# 433hw2.net
KiCad netlist of a schematic drawn in EAGLE
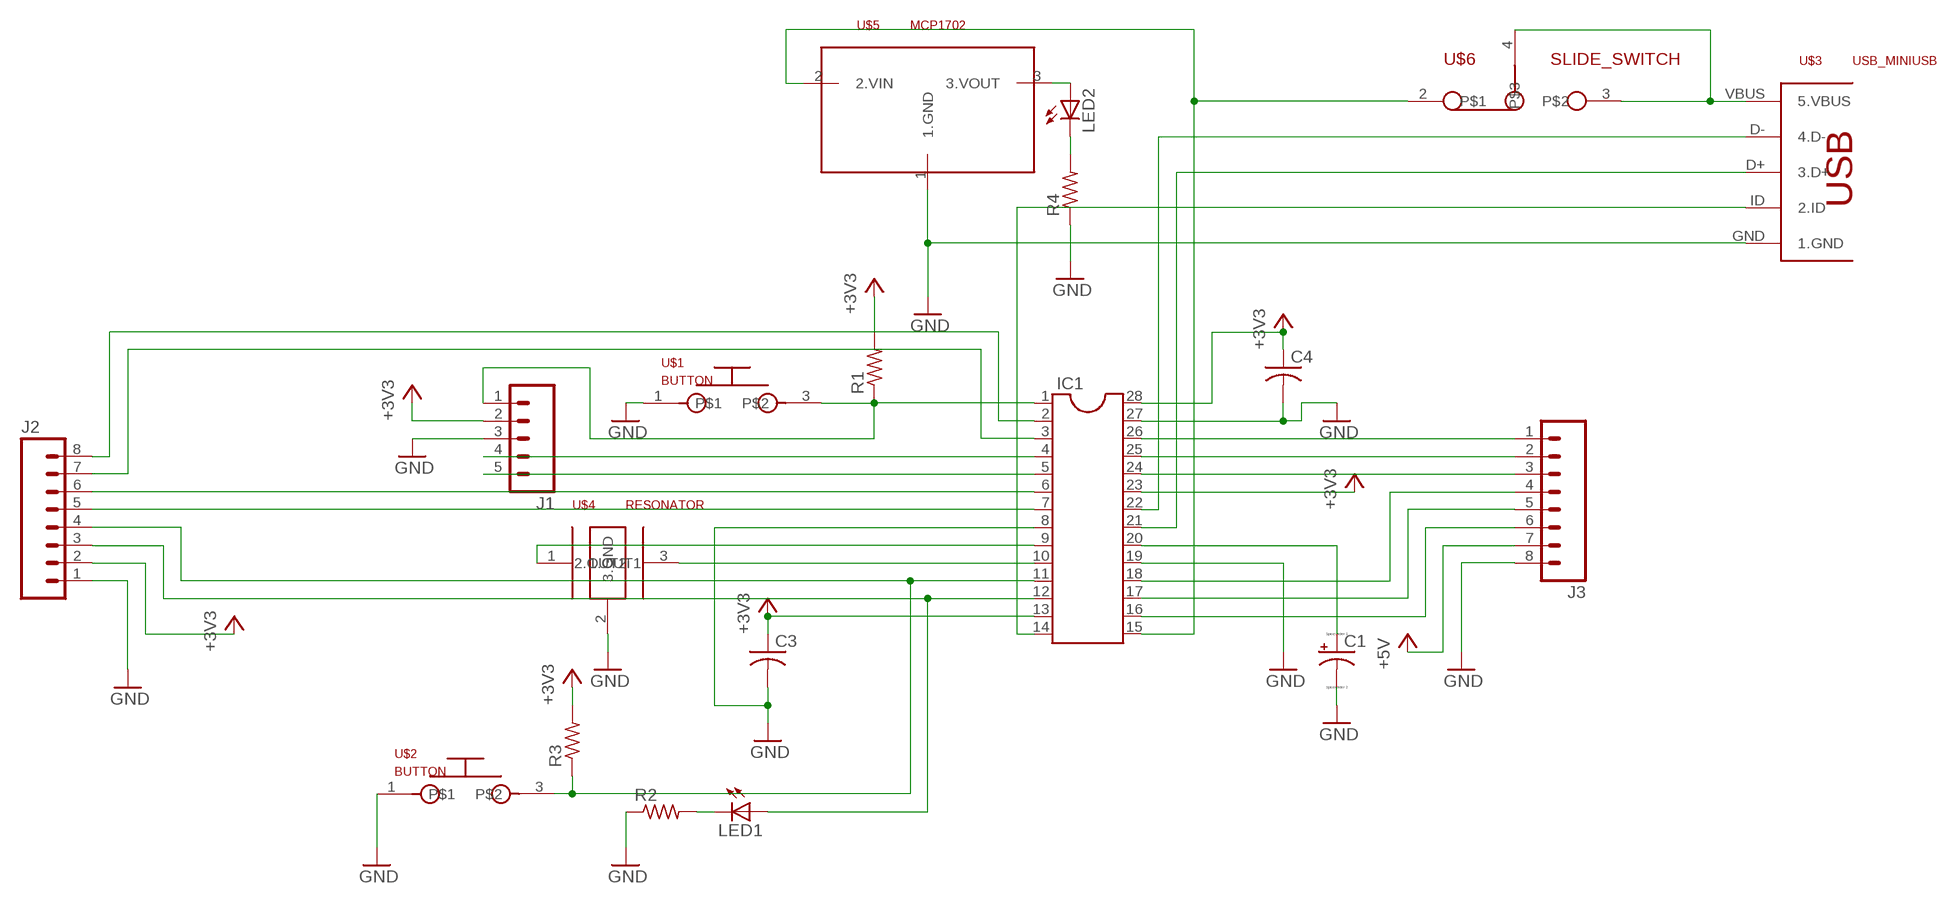
[diagram p0: schematic, sheet 1]

(export (version "E")
  (design (tool "Eeschema 10.0.6"))
  (components
    (comp (ref "C1")
      (value "CPOL-USE2.5-6")
      (footprint "eagle-import:E2,5-6")
      (libsource (lib "eagle-import") (part "CPOL-USE2.5-6"))
    )
    (comp (ref "C3")
      (value "C-US025-025X050")
      (footprint "eagle-import:C025-025X050")
      (libsource (lib "eagle-import") (part "C-US025-025X050"))
    )
    (comp (ref "C4")
      (value "C-US025-025X050")
      (footprint "eagle-import:C025-025X050")
      (libsource (lib "eagle-import") (part "C-US025-025X050"))
    )
    (comp (ref "IC1")
      (value "DIL28-4")
      (footprint "eagle-import:DIL28-4")
      (libsource (lib "eagle-import") (part "DIL28-4"))
    )
    (comp (ref "J1")
      (value "M05PTH")
      (footprint "eagle-import:1X05")
      (libsource (lib "eagle-import") (part "M05PTH"))
    )
    (comp (ref "J2")
      (value "M08")
      (footprint "eagle-import:1X08_ROUND")
      (libsource (lib "eagle-import") (part "M08"))
    )
    (comp (ref "J3")
      (value "M08")
      (footprint "eagle-import:1X08_ROUND")
      (libsource (lib "eagle-import") (part "M08"))
    )
    (comp (ref "LED1")
      (value "LED3MM")
      (footprint "eagle-import:LED3MM")
      (libsource (lib "eagle-import") (part "LED3MM"))
    )
    (comp (ref "LED2")
      (value "LED3MM")
      (footprint "eagle-import:LED3MM")
      (libsource (lib "eagle-import") (part "LED3MM"))
    )
    (comp (ref "R1")
      (value "R-US_0207/7")
      (footprint "eagle-import:0207_7")
      (libsource (lib "eagle-import") (part "R-US_0207/7"))
    )
    (comp (ref "R2")
      (value "R-US_0207/7")
      (footprint "eagle-import:0207_7")
      (libsource (lib "eagle-import") (part "R-US_0207/7"))
    )
    (comp (ref "R3")
      (value "R-US_0207/7")
      (footprint "eagle-import:0207_7")
      (libsource (lib "eagle-import") (part "R-US_0207/7"))
    )
    (comp (ref "R4")
      (value "R-US_0207/7")
      (footprint "eagle-import:0207_7")
      (libsource (lib "eagle-import") (part "R-US_0207/7"))
    )
    (comp (ref "U$1")
      (value "BUTTON")
      (footprint "eagle-import:BUTTON")
      (libsource (lib "eagle-import") (part "BUTTON"))
    )
    (comp (ref "U$2")
      (value "BUTTON")
      (footprint "eagle-import:BUTTON")
      (libsource (lib "eagle-import") (part "BUTTON"))
    )
    (comp (ref "U$3")
      (value "USB_MINIUSB")
      (footprint "eagle-import:USB-MB-H")
      (libsource (lib "eagle-import") (part "USB_MINIUSB"))
    )
    (comp (ref "U$4")
      (value "RESONATOR")
      (footprint "eagle-import:1X03")
      (libsource (lib "eagle-import") (part "RESONATOR"))
    )
    (comp (ref "U$5")
      (value "MCP1702")
      (footprint "eagle-import:TO92")
      (libsource (lib "eagle-import") (part "MCP1702"))
    )
    (comp (ref "U$6")
      (value "SLIDE_SWITCH")
      (footprint "eagle-import:1X05")
      (libsource (lib "eagle-import") (part "SLIDE_SWITCH"))
    )
  )
  (nets
    (net (code "1") (name "+3V3") (class "Default")
      (node (ref "C3") (pin "1") (pinfunction "1_1") (pintype "passive"))
      (node (ref "C4") (pin "1") (pinfunction "1_1") (pintype "passive"))
      (node (ref "IC1") (pin "13") (pinfunction "13_13") (pintype "passive"))
      (node (ref "IC1") (pin "23") (pinfunction "23_23") (pintype "passive"))
      (node (ref "IC1") (pin "28") (pinfunction "28_28") (pintype "passive"))
      (node (ref "J1") (pin "2") (pinfunction "2_2") (pintype "passive"))
      (node (ref "J2") (pin "2") (pinfunction "2_2") (pintype "passive"))
      (node (ref "R1") (pin "2") (pinfunction "2_2") (pintype "passive"))
      (node (ref "R3") (pin "2") (pinfunction "2_2") (pintype "passive"))
    )
    (net (code "2") (name "+5V") (class "Default")
      (node (ref "J3") (pin "7") (pinfunction "7_7") (pintype "passive"))
    )
    (net (code "3") (name "GND") (class "Default")
      (node (ref "C1") (pin "-") (pinfunction "-_-") (pintype "passive"))
      (node (ref "C3") (pin "2") (pinfunction "2_2") (pintype "passive"))
      (node (ref "C4") (pin "2") (pinfunction "2_2") (pintype "passive"))
      (node (ref "IC1") (pin "19") (pinfunction "19_19") (pintype "passive"))
      (node (ref "IC1") (pin "27") (pinfunction "27_27") (pintype "passive"))
      (node (ref "IC1") (pin "8") (pinfunction "8_8") (pintype "passive"))
      (node (ref "J1") (pin "3") (pinfunction "3_3") (pintype "passive"))
      (node (ref "J2") (pin "1") (pinfunction "1_1") (pintype "passive"))
      (node (ref "J3") (pin "8") (pinfunction "8_8") (pintype "passive"))
      (node (ref "R2") (pin "1") (pinfunction "1_1") (pintype "passive"))
      (node (ref "R4") (pin "1") (pinfunction "1_1") (pintype "passive"))
      (node (ref "U$1") (pin "1") (pinfunction "P$1_1") (pintype "bidirectional"))
      (node (ref "U$2") (pin "1") (pinfunction "P$1_1") (pintype "bidirectional"))
      (node (ref "U$3") (pin "GND") (pinfunction "1.GND_GND") (pintype "bidirectional"))
      (node (ref "U$4") (pin "2") (pinfunction "3.GND_2") (pintype "bidirectional"))
      (node (ref "U$5") (pin "1") (pinfunction "1.GND_1") (pintype "bidirectional"))
    )
    (net (code "4") (name "Net-(C1-Pad+)") (class "Default")
      (node (ref "C1") (pin "+") (pinfunction "+_+") (pintype "passive"))
      (node (ref "IC1") (pin "20") (pinfunction "20_20") (pintype "passive"))
    )
    (net (code "5") (name "Net-(IC1-Pad2)") (class "Default")
      (node (ref "IC1") (pin "2") (pinfunction "2_2") (pintype "passive"))
      (node (ref "J2") (pin "8") (pinfunction "8_8") (pintype "passive"))
    )
    (net (code "6") (name "Net-(IC1-Pad3)") (class "Default")
      (node (ref "IC1") (pin "3") (pinfunction "3_3") (pintype "passive"))
      (node (ref "J2") (pin "7") (pinfunction "7_7") (pintype "passive"))
    )
    (net (code "7") (name "Net-(IC1-Pad4)") (class "Default")
      (node (ref "IC1") (pin "4") (pinfunction "4_4") (pintype "passive"))
      (node (ref "J1") (pin "4") (pinfunction "4_4") (pintype "passive"))
    )
    (net (code "8") (name "Net-(IC1-Pad5)") (class "Default")
      (node (ref "IC1") (pin "5") (pinfunction "5_5") (pintype "passive"))
      (node (ref "J1") (pin "5") (pinfunction "5_5") (pintype "passive"))
    )
    (net (code "9") (name "Net-(IC1-Pad6)") (class "Default")
      (node (ref "IC1") (pin "6") (pinfunction "6_6") (pintype "passive"))
      (node (ref "J2") (pin "6") (pinfunction "6_6") (pintype "passive"))
    )
    (net (code "10") (name "Net-(IC1-Pad7)") (class "Default")
      (node (ref "IC1") (pin "7") (pinfunction "7_7") (pintype "passive"))
      (node (ref "J2") (pin "5") (pinfunction "5_5") (pintype "passive"))
    )
    (net (code "11") (name "Net-(IC1-Pad12)") (class "Default")
      (node (ref "IC1") (pin "12") (pinfunction "12_12") (pintype "passive"))
      (node (ref "J2") (pin "3") (pinfunction "3_3") (pintype "passive"))
      (node (ref "LED1") (pin "A") (pinfunction "A_A") (pintype "passive"))
    )
    (net (code "12") (name "Net-(IC1-Pad16)") (class "Default")
      (node (ref "IC1") (pin "16") (pinfunction "16_16") (pintype "passive"))
      (node (ref "J3") (pin "6") (pinfunction "6_6") (pintype "passive"))
    )
    (net (code "13") (name "Net-(IC1-Pad17)") (class "Default")
      (node (ref "IC1") (pin "17") (pinfunction "17_17") (pintype "passive"))
      (node (ref "J3") (pin "5") (pinfunction "5_5") (pintype "passive"))
    )
    (net (code "14") (name "Net-(IC1-Pad18)") (class "Default")
      (node (ref "IC1") (pin "18") (pinfunction "18_18") (pintype "passive"))
      (node (ref "J3") (pin "4") (pinfunction "4_4") (pintype "passive"))
    )
    (net (code "15") (name "Net-(IC1-Pad24)") (class "Default")
      (node (ref "IC1") (pin "24") (pinfunction "24_24") (pintype "passive"))
      (node (ref "J3") (pin "3") (pinfunction "3_3") (pintype "passive"))
    )
    (net (code "16") (name "Net-(IC1-Pad25)") (class "Default")
      (node (ref "IC1") (pin "25") (pinfunction "25_25") (pintype "passive"))
      (node (ref "J3") (pin "2") (pinfunction "2_2") (pintype "passive"))
    )
    (net (code "17") (name "Net-(IC1-Pad26)") (class "Default")
      (node (ref "IC1") (pin "26") (pinfunction "26_26") (pintype "passive"))
      (node (ref "J3") (pin "1") (pinfunction "1_1") (pintype "passive"))
    )
    (net (code "18") (name "Net-(LED1-C)") (class "Default")
      (node (ref "LED1") (pin "K") (pinfunction "C_K") (pintype "passive"))
      (node (ref "R2") (pin "2") (pinfunction "2_2") (pintype "passive"))
    )
    (net (code "19") (name "Net-(LED2-C)") (class "Default")
      (node (ref "LED2") (pin "K") (pinfunction "C_K") (pintype "passive"))
      (node (ref "R4") (pin "2") (pinfunction "2_2") (pintype "passive"))
    )
    (net (code "20") (name "Net-(U$1-P$2)") (class "Default")
      (node (ref "IC1") (pin "1") (pinfunction "1_1") (pintype "passive"))
      (node (ref "J1") (pin "1") (pinfunction "1_1") (pintype "passive"))
      (node (ref "R1") (pin "1") (pinfunction "1_1") (pintype "passive"))
      (node (ref "U$1") (pin "3") (pinfunction "P$2_3") (pintype "bidirectional"))
    )
    (net (code "21") (name "Net-(U$2-P$2)") (class "Default")
      (node (ref "IC1") (pin "11") (pinfunction "11_11") (pintype "passive"))
      (node (ref "J2") (pin "4") (pinfunction "4_4") (pintype "passive"))
      (node (ref "R3") (pin "1") (pinfunction "1_1") (pintype "passive"))
      (node (ref "U$2") (pin "3") (pinfunction "P$2_3") (pintype "bidirectional"))
    )
    (net (code "22") (name "Net-(U$3-2.ID)") (class "Default")
      (node (ref "IC1") (pin "14") (pinfunction "14_14") (pintype "passive"))
      (node (ref "U$3") (pin "ID") (pinfunction "2.ID_ID") (pintype "bidirectional"))
    )
    (net (code "23") (name "Net-(U$3-3.D+)") (class "Default")
      (node (ref "IC1") (pin "21") (pinfunction "21_21") (pintype "passive"))
      (node (ref "U$3") (pin "D+") (pinfunction "3.D+_D+") (pintype "bidirectional"))
    )
    (net (code "24") (name "Net-(U$3-4.D-)") (class "Default")
      (node (ref "IC1") (pin "22") (pinfunction "22_22") (pintype "passive"))
      (node (ref "U$3") (pin "D-") (pinfunction "4.D-_D-") (pintype "bidirectional"))
    )
    (net (code "25") (name "Net-(U$3-5.VBUS)") (class "Default")
      (node (ref "U$3") (pin "VBUS") (pinfunction "5.VBUS_VBUS") (pintype "bidirectional"))
      (node (ref "U$6") (pin "3") (pinfunction "P$2_3") (pintype "bidirectional"))
      (node (ref "U$6") (pin "4") (pinfunction "P$3_4") (pintype "bidirectional"))
    )
    (net (code "26") (name "Net-(U$4-1.OUT1)") (class "Default")
      (node (ref "IC1") (pin "9") (pinfunction "9_9") (pintype "passive"))
      (node (ref "U$4") (pin "1") (pinfunction "1.OUT1_1") (pintype "bidirectional"))
    )
    (net (code "27") (name "Net-(U$4-2.OUT2)") (class "Default")
      (node (ref "IC1") (pin "10") (pinfunction "10_10") (pintype "passive"))
      (node (ref "U$4") (pin "3") (pinfunction "2.OUT2_3") (pintype "bidirectional"))
    )
    (net (code "28") (name "Net-(U$5-2.VIN)") (class "Default")
      (node (ref "IC1") (pin "15") (pinfunction "15_15") (pintype "passive"))
      (node (ref "U$5") (pin "2") (pinfunction "2.VIN_2") (pintype "bidirectional"))
      (node (ref "U$6") (pin "2") (pinfunction "P$1_2") (pintype "bidirectional"))
    )
    (net (code "29") (name "Net-(U$5-3.VOUT)") (class "Default")
      (node (ref "LED2") (pin "A") (pinfunction "A_A") (pintype "passive"))
      (node (ref "U$5") (pin "3") (pinfunction "3.VOUT_3") (pintype "bidirectional"))
    )
  )
)
